# lcheapo-v5.net
KiCad netlist of a schematic drawn in EAGLE
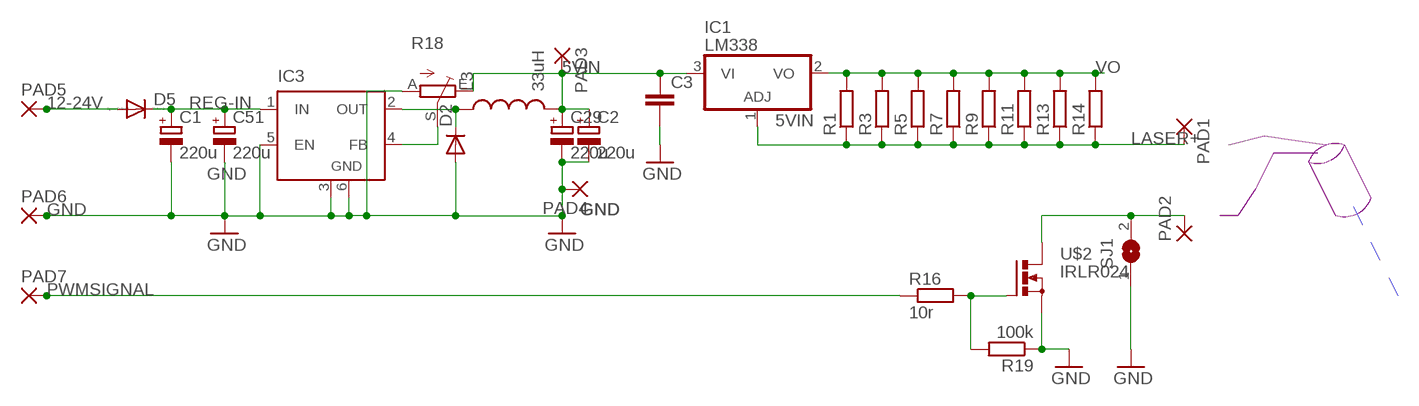
[diagram p0: schematic, sheet 1]

(export (version "E")
  (design (tool "Eeschema 10.0.6"))
  (components
    (comp (ref "C1")
      (value "220u")
      (footprint "eagle-import:E2,5-7")
      (libsource (lib "eagle-import") (part "CPOL-EUE2.5-7"))
    )
    (comp (ref "C2")
      (value "220u")
      (footprint "eagle-import:PANASONIC_D")
      (libsource (lib "eagle-import") (part "CPOL-EUD"))
    )
    (comp (ref "C3")
      (value "C-EUC0603")
      (footprint "eagle-import:C0603")
      (libsource (lib "eagle-import") (part "C-EUC0603"))
    )
    (comp (ref "C29")
      (value "220u")
      (footprint "eagle-import:E2,5-7")
      (libsource (lib "eagle-import") (part "CPOL-EUE2.5-7"))
    )
    (comp (ref "C51")
      (value "220u")
      (footprint "eagle-import:PANASONIC_D")
      (libsource (lib "eagle-import") (part "CPOL-EUD"))
    )
    (comp (ref "D2")
      (value "DIODE-DO-214AC")
      (footprint "eagle-import:DO-214AC")
      (libsource (lib "eagle-import") (part "dp_devices_DIODE-DO-214AC"))
    )
    (comp (ref "D5")
      (value "DIODE-MELF-MLL41")
      (footprint "eagle-import:MELF-MLL41")
      (libsource (lib "eagle-import") (part "DIODE-MELF-MLL41"))
    )
    (comp (ref "IC1")
      (value "LM338")
      (footprint "eagle-import:TO220H")
      (libsource (lib "eagle-import") (part "317T"))
    )
    (comp (ref "IC3")
      (value "LM2596S")
      (footprint "eagle-import:TO263-5")
      (libsource (lib "eagle-import") (part "LM2596S"))
    )
    (comp (ref "L3")
      (value "33uH")
      (footprint "eagle-import:CDRH125")
      (libsource (lib "eagle-import") (part "INDUCTORPWR"))
    )
    (comp (ref "PAD1")
      (value "2,54/1,0")
      (footprint "eagle-import:2,54_1,0")
      (libsource (lib "eagle-import") (part "2,54/1,0"))
    )
    (comp (ref "PAD2")
      (value "2,54/1,0")
      (footprint "eagle-import:2,54_1,0")
      (libsource (lib "eagle-import") (part "2,54/1,0"))
    )
    (comp (ref "PAD3")
      (value "2,54/1,0")
      (footprint "eagle-import:2,54_1,0")
      (libsource (lib "eagle-import") (part "2,54/1,0"))
    )
    (comp (ref "PAD4")
      (value "2,54/1,0")
      (footprint "eagle-import:2,54_1,0")
      (libsource (lib "eagle-import") (part "2,54/1,0"))
    )
    (comp (ref "PAD5")
      (value "2,54/1,1")
      (footprint "eagle-import:2,54_1,1")
      (libsource (lib "eagle-import") (part "2,54/1,1"))
    )
    (comp (ref "PAD6")
      (value "2,54/1,1")
      (footprint "eagle-import:2,54_1,1")
      (libsource (lib "eagle-import") (part "2,54/1,1"))
    )
    (comp (ref "PAD7")
      (value "2,54/1,1")
      (footprint "eagle-import:2,54_1,1")
      (libsource (lib "eagle-import") (part "2,54/1,1"))
    )
    (comp (ref "R1")
      (value "R-EU_R2512")
      (footprint "eagle-import:R2512")
      (libsource (lib "eagle-import") (part "R-EU_R2512"))
    )
    (comp (ref "R3")
      (value "R-EU_R2512")
      (footprint "eagle-import:R2512")
      (libsource (lib "eagle-import") (part "R-EU_R2512"))
    )
    (comp (ref "R5")
      (value "R-EU_R2512")
      (footprint "eagle-import:R2512")
      (libsource (lib "eagle-import") (part "R-EU_R2512"))
    )
    (comp (ref "R7")
      (value "R-EU_R2512")
      (footprint "eagle-import:R2512")
      (libsource (lib "eagle-import") (part "R-EU_R2512"))
    )
    (comp (ref "R9")
      (value "R-EU_R2512")
      (footprint "eagle-import:R2512")
      (libsource (lib "eagle-import") (part "R-EU_R2512"))
    )
    (comp (ref "R11")
      (value "R-EU_R2512")
      (footprint "eagle-import:R2512")
      (libsource (lib "eagle-import") (part "R-EU_R2512"))
    )
    (comp (ref "R13")
      (value "R-EU_R2512")
      (footprint "eagle-import:R2512")
      (libsource (lib "eagle-import") (part "R-EU_R2512"))
    )
    (comp (ref "R14")
      (value "R-EU_R2512")
      (footprint "eagle-import:R2512")
      (libsource (lib "eagle-import") (part "R-EU_R2512"))
    )
    (comp (ref "R16")
      (value "10r")
      (footprint "eagle-import:R1206")
      (libsource (lib "eagle-import") (part "R-EU_R1206"))
    )
    (comp (ref "R18")
      (value "TRIM_EU-RJ9W")
      (footprint "eagle-import:RJ9W")
      (libsource (lib "eagle-import") (part "TRIM_EU-RJ9W"))
    )
    (comp (ref "R19")
      (value "100k")
      (footprint "eagle-import:R1206")
      (libsource (lib "eagle-import") (part "R-EU_R1206"))
    )
    (comp (ref "SJ1") (value "SJ") (footprint "eagle-import:SJ") (libsource (lib "eagle-import") (part "SJ")))
    (comp (ref "U$2")
      (value "IRLR024")
      (footprint "eagle-import:D-PAK_TO252AA")
      (libsource (lib "eagle-import") (part "N-POWER-MOSFETDPAK-MOSFET"))
    )
  )
  (nets
    (net (code "1") (name "/5VIN") (class "Default")
      (node (ref "C2") (pin "+") (pinfunction "+_+") (pintype "passive"))
      (node (ref "C29") (pin "+") (pinfunction "+_+") (pintype "passive"))
      (node (ref "C3") (pin "1") (pinfunction "1_1") (pintype "passive"))
      (node (ref "IC1") (pin "3") (pinfunction "VI_3") (pintype "input"))
      (node (ref "L3") (pin "2") (pinfunction "2_2") (pintype "passive"))
      (node (ref "PAD3") (pin "1") (pinfunction "P_1") (pintype "passive"))
      (node (ref "R18") (pin "E") (pinfunction "E_E") (pintype "passive"))
    )
    (net (code "2") (name "/12-24V") (class "Default")
      (node (ref "D5") (pin "A") (pinfunction "A_A") (pintype "passive"))
      (node (ref "PAD5") (pin "1") (pinfunction "P_1") (pintype "passive"))
    )
    (net (code "3") (name "/LASER+") (class "Default")
      (node (ref "IC1") (pin "1") (pinfunction "ADJ_1") (pintype "input"))
      (node (ref "PAD1") (pin "1") (pinfunction "P_1") (pintype "passive"))
      (node (ref "R1") (pin "1") (pinfunction "1_1") (pintype "passive"))
      (node (ref "R11") (pin "1") (pinfunction "1_1") (pintype "passive"))
      (node (ref "R13") (pin "1") (pinfunction "1_1") (pintype "passive"))
      (node (ref "R14") (pin "1") (pinfunction "1_1") (pintype "passive"))
      (node (ref "R3") (pin "1") (pinfunction "1_1") (pintype "passive"))
      (node (ref "R5") (pin "1") (pinfunction "1_1") (pintype "passive"))
      (node (ref "R7") (pin "1") (pinfunction "1_1") (pintype "passive"))
      (node (ref "R9") (pin "1") (pinfunction "1_1") (pintype "passive"))
    )
    (net (code "4") (name "/PWMSIGNAL") (class "Default")
      (node (ref "PAD7") (pin "1") (pinfunction "P_1") (pintype "passive"))
      (node (ref "R16") (pin "1") (pinfunction "1_1") (pintype "passive"))
    )
    (net (code "5") (name "/REG-IN") (class "Default")
      (node (ref "C1") (pin "+") (pinfunction "+_+") (pintype "passive"))
      (node (ref "C51") (pin "+") (pinfunction "+_+") (pintype "passive"))
      (node (ref "D5") (pin "C") (pinfunction "C_C") (pintype "passive"))
      (node (ref "IC3") (pin "1") (pinfunction "IN_1") (pintype "input"))
    )
    (net (code "6") (name "/VO") (class "Default")
      (node (ref "IC1") (pin "2") (pinfunction "VO_2") (pintype "passive"))
      (node (ref "R1") (pin "2") (pinfunction "2_2") (pintype "passive"))
      (node (ref "R11") (pin "2") (pinfunction "2_2") (pintype "passive"))
      (node (ref "R13") (pin "2") (pinfunction "2_2") (pintype "passive"))
      (node (ref "R14") (pin "2") (pinfunction "2_2") (pintype "passive"))
      (node (ref "R3") (pin "2") (pinfunction "2_2") (pintype "passive"))
      (node (ref "R5") (pin "2") (pinfunction "2_2") (pintype "passive"))
      (node (ref "R7") (pin "2") (pinfunction "2_2") (pintype "passive"))
      (node (ref "R9") (pin "2") (pinfunction "2_2") (pintype "passive"))
    )
    (net (code "7") (name "GND") (class "Default")
      (node (ref "C1") (pin "-") (pinfunction "-_-") (pintype "passive"))
      (node (ref "C2") (pin "-") (pinfunction "-_-") (pintype "passive"))
      (node (ref "C29") (pin "-") (pinfunction "-_-") (pintype "passive"))
      (node (ref "C3") (pin "2") (pinfunction "2_2") (pintype "passive"))
      (node (ref "C51") (pin "-") (pinfunction "-_-") (pintype "passive"))
      (node (ref "D2") (pin "2") (pinfunction "A_2") (pintype "passive"))
      (node (ref "IC3") (pin "3") (pinfunction "GND_3") (pintype "power_in"))
      (node (ref "IC3") (pin "5") (pinfunction "EN_5") (pintype "input"))
      (node (ref "IC3") (pin "6") (pinfunction "GND_6") (pintype "power_in"))
      (node (ref "PAD4") (pin "1") (pinfunction "P_1") (pintype "passive"))
      (node (ref "PAD6") (pin "1") (pinfunction "P_1") (pintype "passive"))
      (node (ref "R18") (pin "A") (pinfunction "A_A") (pintype "passive"))
      (node (ref "R19") (pin "1") (pinfunction "1_1") (pintype "passive"))
      (node (ref "SJ1") (pin "1") (pinfunction "1_1") (pintype "passive"))
      (node (ref "U$2") (pin "3") (pinfunction "S_3") (pintype "passive"))
    )
    (net (code "8") (name "Net-(D2-C)") (class "Default")
      (node (ref "D2") (pin "1") (pinfunction "C_1") (pintype "passive"))
      (node (ref "IC3") (pin "2") (pinfunction "OUT_2") (pintype "output"))
      (node (ref "L3") (pin "1") (pinfunction "1_1") (pintype "passive"))
    )
    (net (code "9") (name "Net-(IC3-FB)") (class "Default")
      (node (ref "IC3") (pin "4") (pinfunction "FB_4") (pintype "input"))
      (node (ref "R18") (pin "S") (pinfunction "S_S") (pintype "passive"))
    )
    (net (code "10") (name "Net-(PAD2-P)") (class "Default")
      (node (ref "PAD2") (pin "1") (pinfunction "P_1") (pintype "passive"))
      (node (ref "SJ1") (pin "2") (pinfunction "2_2") (pintype "passive"))
      (node (ref "U$2") (pin "4") (pinfunction "D_4") (pintype "passive"))
    )
    (net (code "11") (name "Net-(U$2-G)") (class "Default")
      (node (ref "R16") (pin "2") (pinfunction "2_2") (pintype "passive"))
      (node (ref "R19") (pin "2") (pinfunction "2_2") (pintype "passive"))
      (node (ref "U$2") (pin "1") (pinfunction "G_1") (pintype "passive"))
    )
  )
)
